# SENSORY_BRIDGE.net
KiCad netlist of a schematic drawn in EAGLE
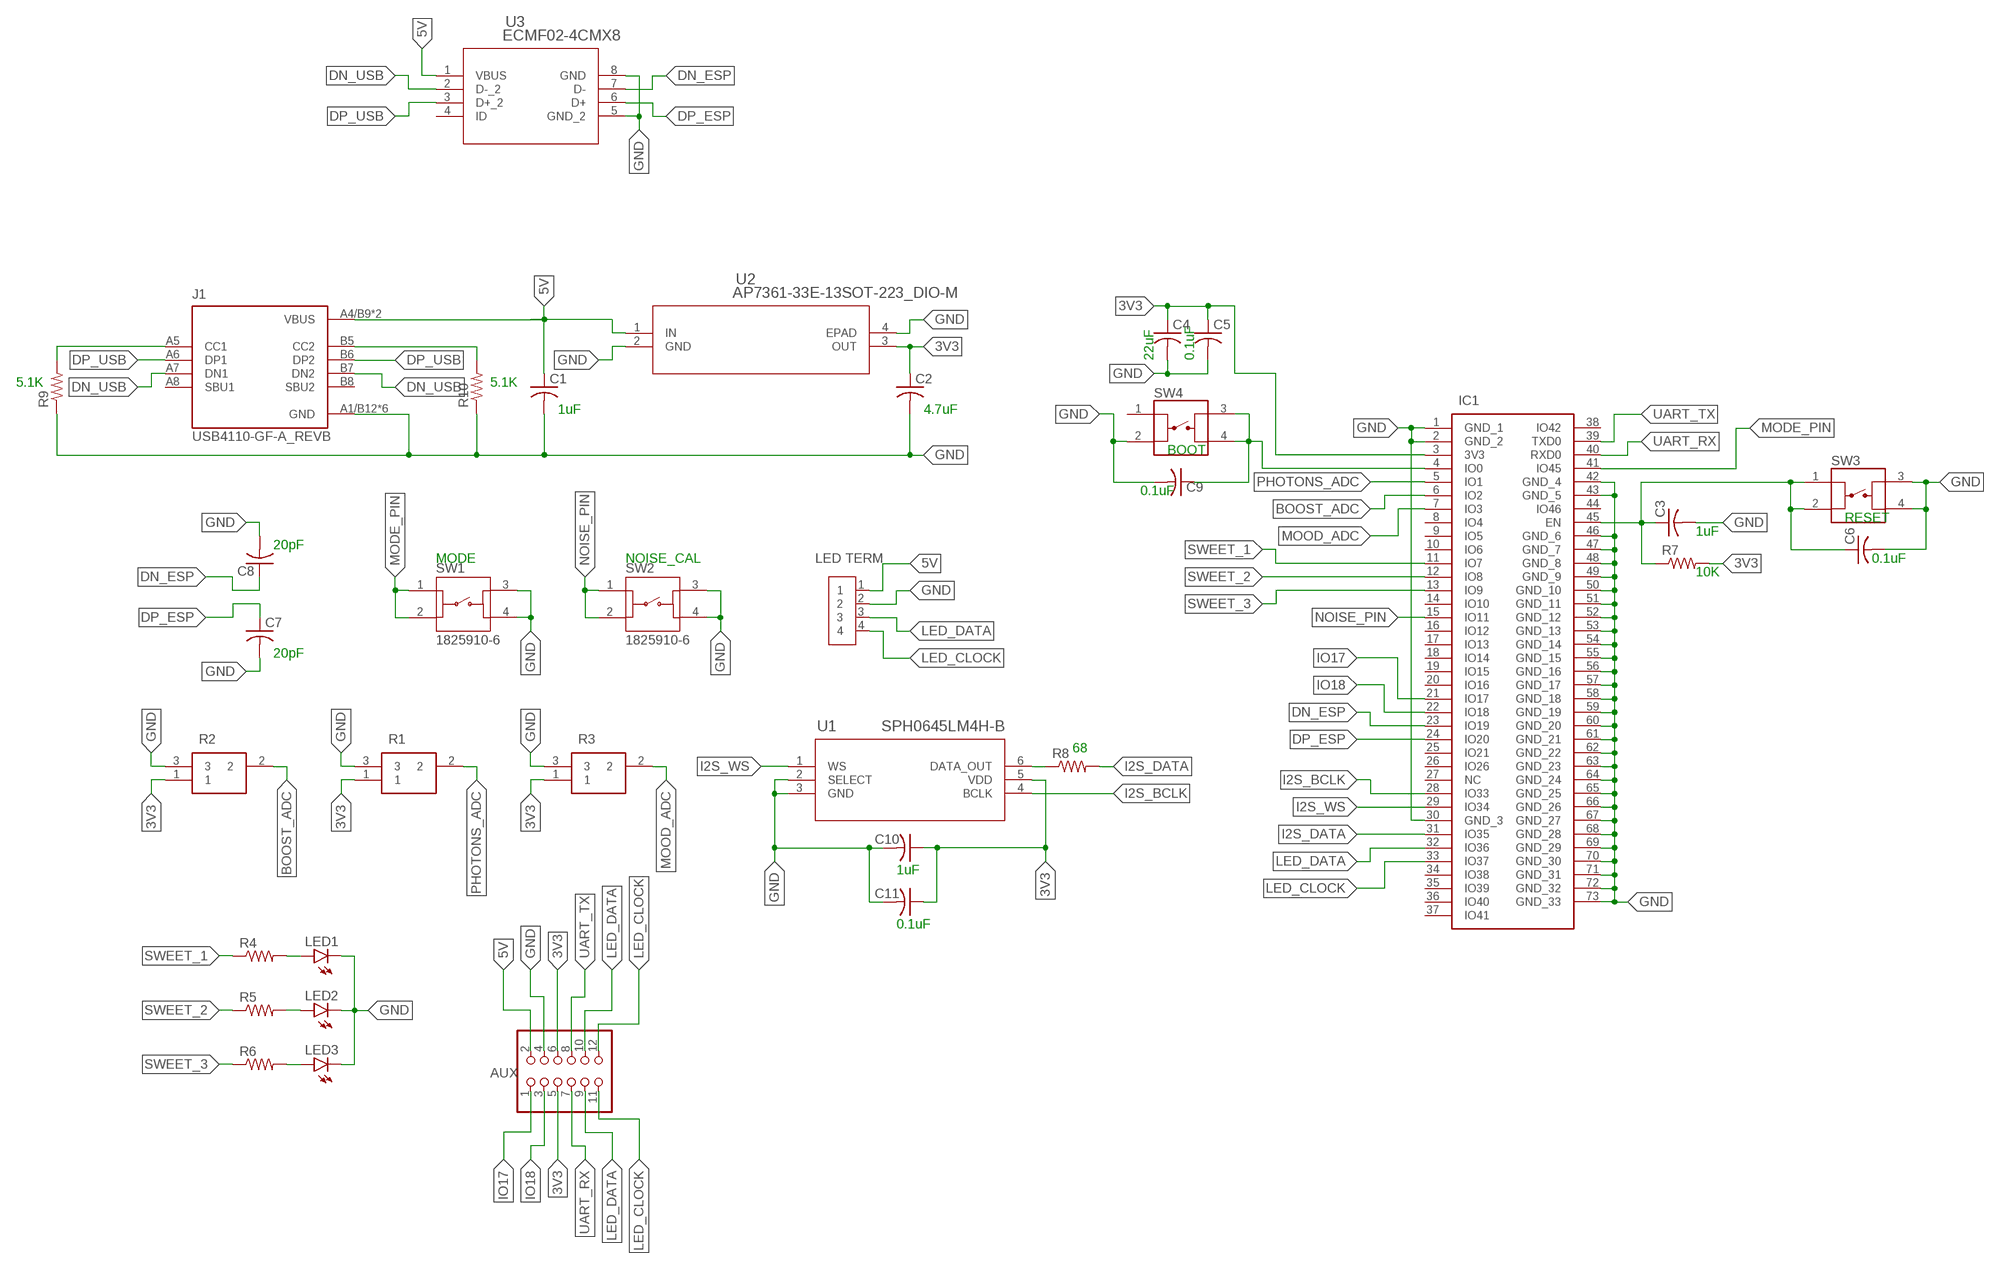
[diagram p0: schematic, sheet 1]

(export (version "E")
  (design (tool "Eeschema 10.0.6"))
  (components
    (comp (ref "C1")
      (value "C-USC0805K")
      (footprint "eagle-import:C0805K")
      (libsource (lib "eagle-import") (part "C-USC0805K"))
    )
    (comp (ref "C2")
      (value "C-USC0805K")
      (footprint "eagle-import:C0805K")
      (libsource (lib "eagle-import") (part "C-USC0805K"))
    )
    (comp (ref "C3")
      (value "C-USC0805K")
      (footprint "eagle-import:C0805K")
      (libsource (lib "eagle-import") (part "C-USC0805K"))
    )
    (comp (ref "C4")
      (value "C-USC0805K")
      (footprint "eagle-import:C0805K")
      (libsource (lib "eagle-import") (part "C-USC0805K"))
    )
    (comp (ref "C5")
      (value "C-USC0805K")
      (footprint "eagle-import:C0805K")
      (libsource (lib "eagle-import") (part "C-USC0805K"))
    )
    (comp (ref "C6")
      (value "C-USC0805K")
      (footprint "eagle-import:C0805K")
      (libsource (lib "eagle-import") (part "C-USC0805K"))
    )
    (comp (ref "C7")
      (value "C-USC0805K")
      (footprint "eagle-import:C0805K")
      (libsource (lib "eagle-import") (part "C-USC0805K"))
    )
    (comp (ref "C8")
      (value "C-USC0805K")
      (footprint "eagle-import:C0805K")
      (libsource (lib "eagle-import") (part "C-USC0805K"))
    )
    (comp (ref "C9")
      (value "C-USC0805K")
      (footprint "eagle-import:C0805K")
      (libsource (lib "eagle-import") (part "C-USC0805K"))
    )
    (comp (ref "C10")
      (value "C-USC0805K")
      (footprint "eagle-import:C0805K")
      (libsource (lib "eagle-import") (part "C-USC0805K"))
    )
    (comp (ref "C11")
      (value "C-USC0805K")
      (footprint "eagle-import:C0805K")
      (libsource (lib "eagle-import") (part "C-USC0805K"))
    )
    (comp (ref "IC1")
      (value "ESP32-S2-MINI-1-N4R2")
      (footprint "eagle-import:ESP32S2MINI1N4R2")
      (fields (field (name "MOUSER_PART_NUMBER") "356-ESP32S2MINI1N4R2"))
      (libsource (lib "eagle-import") (part "ESP32-S2-MINI-1-N4R2"))
    )
    (comp (ref "J1")
      (value "USB4110-GF-A_REVB")
      (footprint "eagle-import:GCT_USB4110-GF-A_REVB")
      (fields
        (field (name "DIGI-KEY_PART_NUMBER") "2073-USB4110-GF-A-1-ND")
        (field (name "MF") "GCT")
        (field (name "MP") "USB4110-GF-A")
      )
      (libsource (lib "eagle-import") (part "USB4110-GF-A_REVB"))
    )
    (comp (ref "J2")
      (value "796949-4")
      (footprint "eagle-import:TE_796949-4")
      (fields (field (name "DIGI-KEY_PART_NUMBER") "796949-4-ND") (field (name "MF") "TE Connectivity"))
      (libsource (lib "eagle-import") (part "796949-4"))
    )
    (comp (ref "JP1")
      (value "PINHD-2X6")
      (footprint "eagle-import:2X06")
      (libsource (lib "eagle-import") (part "PINHD-2X6"))
    )
    (comp (ref "LED1")
      (value "LED3MM")
      (footprint "eagle-import:LED3MM")
      (libsource (lib "eagle-import") (part "LED3MM"))
    )
    (comp (ref "LED2")
      (value "LED3MM")
      (footprint "eagle-import:LED3MM")
      (libsource (lib "eagle-import") (part "LED3MM"))
    )
    (comp (ref "LED3")
      (value "LED3MM")
      (footprint "eagle-import:LED3MM")
      (libsource (lib "eagle-import") (part "LED3MM"))
    )
    (comp (ref "R1")
      (value "3386P-1-103LF")
      (footprint "eagle-import:3386P_1")
      (fields (field (name "MOUSER_PART_NUMBER") "652-3386P-1-103LF"))
      (libsource (lib "eagle-import") (part "3386P-1-103LF"))
    )
    (comp (ref "R2")
      (value "3386P-1-103LF")
      (footprint "eagle-import:3386P_1")
      (fields (field (name "MOUSER_PART_NUMBER") "652-3386P-1-103LF"))
      (libsource (lib "eagle-import") (part "3386P-1-103LF"))
    )
    (comp (ref "R3")
      (value "3386P-1-103LF")
      (footprint "eagle-import:3386P_1")
      (fields (field (name "MOUSER_PART_NUMBER") "652-3386P-1-103LF"))
      (libsource (lib "eagle-import") (part "3386P-1-103LF"))
    )
    (comp (ref "R4")
      (value "R-US_R0805")
      (footprint "eagle-import:R0805")
      (libsource (lib "eagle-import") (part "R-US_R0805"))
    )
    (comp (ref "R5")
      (value "R-US_R0805")
      (footprint "eagle-import:R0805")
      (libsource (lib "eagle-import") (part "R-US_R0805"))
    )
    (comp (ref "R6")
      (value "R-US_R0805")
      (footprint "eagle-import:R0805")
      (libsource (lib "eagle-import") (part "R-US_R0805"))
    )
    (comp (ref "R7")
      (value "R-US_R0805")
      (footprint "eagle-import:R0805")
      (libsource (lib "eagle-import") (part "R-US_R0805"))
    )
    (comp (ref "R8")
      (value "R-US_R0805")
      (footprint "eagle-import:R0805")
      (libsource (lib "eagle-import") (part "R-US_R0805"))
    )
    (comp (ref "R9")
      (value "R-US_R0805")
      (footprint "eagle-import:R0805")
      (libsource (lib "eagle-import") (part "R-US_R0805"))
    )
    (comp (ref "R10")
      (value "R-US_R0805")
      (footprint "eagle-import:R0805")
      (libsource (lib "eagle-import") (part "R-US_R0805"))
    )
    (comp (ref "SW1")
      (value "1825910-6")
      (footprint "eagle-import:SW_1825910-6-4")
      (fields (field (name "DIGI-KEY_PART_NUMBER") "450-1650-ND") (field (name "MF") "TE Connectivity"))
      (libsource (lib "eagle-import") (part "1825910-6"))
    )
    (comp (ref "SW2")
      (value "1825910-6")
      (footprint "eagle-import:SW_1825910-6-4")
      (fields (field (name "DIGI-KEY_PART_NUMBER") "450-1650-ND") (field (name "MF") "TE Connectivity"))
      (libsource (lib "eagle-import") (part "1825910-6"))
    )
    (comp (ref "SW3")
      (value "PTS525SM15SMTR2LFS")
      (footprint "eagle-import:SW_PTS525SM15SMTR2LFS")
      (fields
        (field (name "DIGI-KEY_PART_NUMBER") "CKN9104CT-ND")
        (field (name "MF") "C&K")
        (field (name "MP") "PTS525SM15SMTR2 LFS")
      )
      (libsource (lib "eagle-import") (part "PTS525SM15SMTR2LFS"))
    )
    (comp (ref "SW4")
      (value "PTS525SM15SMTR2LFS")
      (footprint "eagle-import:SW_PTS525SM15SMTR2LFS")
      (fields
        (field (name "DIGI-KEY_PART_NUMBER") "CKN9104CT-ND")
        (field (name "MF") "C&K")
        (field (name "MP") "PTS525SM15SMTR2 LFS")
      )
      (libsource (lib "eagle-import") (part "PTS525SM15SMTR2LFS"))
    )
    (comp (ref "U1")
      (value "SPH0645LM4H-B")
      (footprint "eagle-import:SPH0645LM4H-B_KNO")
      (fields (field (name "COPYRIGHT") "Copyright (C) 2022 Ultra Librarian. All rights reserved."))
      (libsource (lib "eagle-import") (part "SPH0645LM4H-B"))
    )
    (comp (ref "U2")
      (value "AP7361-33E-13SOT-223_DIO-M")
      (footprint "eagle-import:SOT-223_DIO-M")
      (fields
        (field (name "MANUFACTURER_PART_NUMBER") "AP7361-33E-13")
        (field (name "COPYRIGHT") "Copyright (C) 2022 Ultra Librarian. All rights reserved.")
      )
      (libsource (lib "eagle-import") (part "AP7361-33E-13SOT-223_DIO-M"))
    )
    (comp (ref "U3")
      (value "ECMF02-4CMX8")
      (footprint "eagle-import:MICRO_QFN-8L_STM")
      (fields (field (name "COPYRIGHT") "Copyright (C) 2022 Ultra Librarian. All rights reserved."))
      (libsource (lib "eagle-import") (part "ECMF02-4CMX8"))
    )
  )
  (nets
    (net (code "1") (name "3V3") (class "Default")
      (node (ref "C10") (pin "1") (pinfunction "1_1") (pintype "passive"))
      (node (ref "C11") (pin "1") (pinfunction "1_1") (pintype "passive"))
      (node (ref "C2") (pin "1") (pinfunction "1_1") (pintype "passive"))
      (node (ref "C4") (pin "1") (pinfunction "1_1") (pintype "passive"))
      (node (ref "C5") (pin "1") (pinfunction "1_1") (pintype "passive"))
      (node (ref "IC1") (pin "3") (pinfunction "3V3_3") (pintype "bidirectional"))
      (node (ref "JP1") (pin "5") (pinfunction "5_5") (pintype "passive"))
      (node (ref "JP1") (pin "6") (pinfunction "6_6") (pintype "passive"))
      (node (ref "R1") (pin "1") (pinfunction "1_1") (pintype "bidirectional"))
      (node (ref "R2") (pin "1") (pinfunction "1_1") (pintype "bidirectional"))
      (node (ref "R3") (pin "1") (pinfunction "1_1") (pintype "bidirectional"))
      (node (ref "R7") (pin "2") (pinfunction "2_2") (pintype "passive"))
      (node (ref "U1") (pin "5") (pinfunction "VDD_5") (pintype "power_in"))
      (node (ref "U2") (pin "3") (pinfunction "OUT_3") (pintype "output"))
    )
    (net (code "2") (name "5V") (class "Default")
      (node (ref "C1") (pin "1") (pinfunction "1_1") (pintype "passive"))
      (node (ref "J1") (pin "A4/B9") (pinfunction "VBUS_A4/B9") (pintype "power_in"))
      (node (ref "J1") (pin "B4/A9") (pinfunction "VBUS_B4/A9") (pintype "power_in"))
      (node (ref "J2") (pin "1") (pinfunction "1_1") (pintype "passive"))
      (node (ref "JP1") (pin "2") (pinfunction "2_2") (pintype "passive"))
      (node (ref "U2") (pin "1") (pinfunction "IN_1") (pintype "input"))
      (node (ref "U3") (pin "1") (pinfunction "VBUS_1") (pintype "power_in"))
    )
    (net (code "3") (name "BOOST_ADC") (class "Default")
      (node (ref "IC1") (pin "6") (pinfunction "IO2_6") (pintype "bidirectional"))
      (node (ref "R2") (pin "2") (pinfunction "2_2") (pintype "bidirectional"))
    )
    (net (code "4") (name "DN_ESP") (class "Default")
      (node (ref "C8") (pin "1") (pinfunction "1_1") (pintype "passive"))
      (node (ref "IC1") (pin "23") (pinfunction "IO19_23") (pintype "bidirectional"))
      (node (ref "U3") (pin "7") (pinfunction "D-_7") (pintype "bidirectional"))
    )
    (net (code "5") (name "DN_USB") (class "Default")
      (node (ref "J1") (pin "A7") (pinfunction "DN1_A7") (pintype "bidirectional"))
      (node (ref "J1") (pin "B7") (pinfunction "DN2_B7") (pintype "bidirectional"))
      (node (ref "U3") (pin "2") (pinfunction "D-_2_2") (pintype "bidirectional"))
    )
    (net (code "6") (name "DP_ESP") (class "Default")
      (node (ref "C7") (pin "1") (pinfunction "1_1") (pintype "passive"))
      (node (ref "IC1") (pin "24") (pinfunction "IO20_24") (pintype "bidirectional"))
      (node (ref "U3") (pin "6") (pinfunction "D+_6") (pintype "bidirectional"))
    )
    (net (code "7") (name "DP_USB") (class "Default")
      (node (ref "J1") (pin "A6") (pinfunction "DP1_A6") (pintype "bidirectional"))
      (node (ref "J1") (pin "B6") (pinfunction "DP2_B6") (pintype "bidirectional"))
      (node (ref "U3") (pin "3") (pinfunction "D+_2_3") (pintype "bidirectional"))
    )
    (net (code "8") (name "GND") (class "Default")
      (node (ref "C1") (pin "2") (pinfunction "2_2") (pintype "passive"))
      (node (ref "C10") (pin "2") (pinfunction "2_2") (pintype "passive"))
      (node (ref "C11") (pin "2") (pinfunction "2_2") (pintype "passive"))
      (node (ref "C2") (pin "2") (pinfunction "2_2") (pintype "passive"))
      (node (ref "C3") (pin "2") (pinfunction "2_2") (pintype "passive"))
      (node (ref "C4") (pin "2") (pinfunction "2_2") (pintype "passive"))
      (node (ref "C5") (pin "2") (pinfunction "2_2") (pintype "passive"))
      (node (ref "C6") (pin "2") (pinfunction "2_2") (pintype "passive"))
      (node (ref "C7") (pin "2") (pinfunction "2_2") (pintype "passive"))
      (node (ref "C8") (pin "2") (pinfunction "2_2") (pintype "passive"))
      (node (ref "C9") (pin "2") (pinfunction "2_2") (pintype "passive"))
      (node (ref "IC1") (pin "1") (pinfunction "GND_1_1") (pintype "bidirectional"))
      (node (ref "IC1") (pin "2") (pinfunction "GND_2_2") (pintype "bidirectional"))
      (node (ref "IC1") (pin "30") (pinfunction "GND_3_30") (pintype "bidirectional"))
      (node (ref "IC1") (pin "42") (pinfunction "GND_4_42") (pintype "bidirectional"))
      (node (ref "IC1") (pin "43") (pinfunction "GND_5_43") (pintype "bidirectional"))
      (node (ref "IC1") (pin "46") (pinfunction "GND_6_46") (pintype "bidirectional"))
      (node (ref "IC1") (pin "47") (pinfunction "GND_7_47") (pintype "bidirectional"))
      (node (ref "IC1") (pin "48") (pinfunction "GND_8_48") (pintype "bidirectional"))
      (node (ref "IC1") (pin "49") (pinfunction "GND_9_49") (pintype "bidirectional"))
      (node (ref "IC1") (pin "50") (pinfunction "GND_10_50") (pintype "bidirectional"))
      (node (ref "IC1") (pin "51") (pinfunction "GND_11_51") (pintype "bidirectional"))
      (node (ref "IC1") (pin "52") (pinfunction "GND_12_52") (pintype "bidirectional"))
      (node (ref "IC1") (pin "53") (pinfunction "GND_13_53") (pintype "bidirectional"))
      (node (ref "IC1") (pin "54") (pinfunction "GND_14_54") (pintype "bidirectional"))
      (node (ref "IC1") (pin "55") (pinfunction "GND_15_55") (pintype "bidirectional"))
      (node (ref "IC1") (pin "56") (pinfunction "GND_16_56") (pintype "bidirectional"))
      (node (ref "IC1") (pin "57") (pinfunction "GND_17_57") (pintype "bidirectional"))
      (node (ref "IC1") (pin "58") (pinfunction "GND_18_58") (pintype "bidirectional"))
      (node (ref "IC1") (pin "59") (pinfunction "GND_19_59") (pintype "bidirectional"))
      (node (ref "IC1") (pin "60") (pinfunction "GND_20_60") (pintype "bidirectional"))
      (node (ref "IC1") (pin "61") (pinfunction "GND_21_61") (pintype "bidirectional"))
      (node (ref "IC1") (pin "62") (pinfunction "GND_22_62") (pintype "bidirectional"))
      (node (ref "IC1") (pin "63") (pinfunction "GND_23_63") (pintype "bidirectional"))
      (node (ref "IC1") (pin "64") (pinfunction "GND_24_64") (pintype "bidirectional"))
      (node (ref "IC1") (pin "65") (pinfunction "GND_25_65") (pintype "bidirectional"))
      (node (ref "IC1") (pin "66") (pinfunction "GND_26_66") (pintype "bidirectional"))
      (node (ref "IC1") (pin "67") (pinfunction "GND_27_67") (pintype "bidirectional"))
      (node (ref "IC1") (pin "68") (pinfunction "GND_28_68") (pintype "bidirectional"))
      (node (ref "IC1") (pin "69") (pinfunction "GND_29_69") (pintype "bidirectional"))
      (node (ref "IC1") (pin "70") (pinfunction "GND_30_70") (pintype "bidirectional"))
      (node (ref "IC1") (pin "71") (pinfunction "GND_31_71") (pintype "bidirectional"))
      (node (ref "IC1") (pin "72") (pinfunction "GND_32_72") (pintype "bidirectional"))
      (node (ref "IC1") (pin "73") (pinfunction "GND_33_73") (pintype "bidirectional"))
      (node (ref "J1") (pin "A1/B12") (pinfunction "GND_A1/B12") (pintype "power_in"))
      (node (ref "J1") (pin "B1/A12") (pinfunction "GND_B1/A12") (pintype "power_in"))
      (node (ref "J1") (pin "S1") (pinfunction "GND_S1") (pintype "power_in"))
      (node (ref "J1") (pin "S2") (pinfunction "GND_S2") (pintype "power_in"))
      (node (ref "J1") (pin "S3") (pinfunction "GND_S3") (pintype "power_in"))
      (node (ref "J1") (pin "S4") (pinfunction "GND_S4") (pintype "power_in"))
      (node (ref "J2") (pin "2") (pinfunction "2_2") (pintype "passive"))
      (node (ref "JP1") (pin "4") (pinfunction "4_4") (pintype "passive"))
      (node (ref "LED1") (pin "K") (pinfunction "C_K") (pintype "passive"))
      (node (ref "LED2") (pin "K") (pinfunction "C_K") (pintype "passive"))
      (node (ref "LED3") (pin "K") (pinfunction "C_K") (pintype "passive"))
      (node (ref "R1") (pin "3") (pinfunction "3_3") (pintype "bidirectional"))
      (node (ref "R10") (pin "1") (pinfunction "1_1") (pintype "passive"))
      (node (ref "R2") (pin "3") (pinfunction "3_3") (pintype "bidirectional"))
      (node (ref "R3") (pin "3") (pinfunction "3_3") (pintype "bidirectional"))
      (node (ref "R9") (pin "1") (pinfunction "1_1") (pintype "passive"))
      (node (ref "SW1") (pin "3") (pinfunction "3_3") (pintype "passive"))
      (node (ref "SW1") (pin "4") (pinfunction "4_4") (pintype "passive"))
      (node (ref "SW2") (pin "3") (pinfunction "3_3") (pintype "passive"))
      (node (ref "SW2") (pin "4") (pinfunction "4_4") (pintype "passive"))
      (node (ref "SW3") (pin "3") (pinfunction "3_3") (pintype "passive"))
      (node (ref "SW3") (pin "4") (pinfunction "4_4") (pintype "passive"))
      (node (ref "SW4") (pin "2") (pinfunction "2_2") (pintype "passive"))
      (node (ref "U1") (pin "2") (pinfunction "SELECT_2") (pintype "input"))
      (node (ref "U1") (pin "3") (pinfunction "GND_3") (pintype "passive"))
      (node (ref "U2") (pin "2") (pinfunction "GND_2") (pintype "power_in"))
      (node (ref "U2") (pin "4") (pinfunction "EPAD_4") (pintype "passive"))
      (node (ref "U3") (pin "5") (pinfunction "GND_2_5") (pintype "passive"))
      (node (ref "U3") (pin "8") (pinfunction "GND_8") (pintype "passive"))
    )
    (net (code "9") (name "I2S_BCLK") (class "Default")
      (node (ref "IC1") (pin "28") (pinfunction "IO33_28") (pintype "bidirectional"))
      (node (ref "U1") (pin "4") (pinfunction "BCLK_4") (pintype "input"))
    )
    (net (code "10") (name "I2S_DATA") (class "Default")
      (node (ref "IC1") (pin "31") (pinfunction "IO35_31") (pintype "bidirectional"))
      (node (ref "R8") (pin "2") (pinfunction "2_2") (pintype "passive"))
    )
    (net (code "11") (name "I2S_WS") (class "Default")
      (node (ref "IC1") (pin "29") (pinfunction "IO34_29") (pintype "bidirectional"))
      (node (ref "U1") (pin "1") (pinfunction "WS_1") (pintype "input"))
    )
    (net (code "12") (name "IO17") (class "Default")
      (node (ref "IC1") (pin "21") (pinfunction "IO17_21") (pintype "bidirectional"))
      (node (ref "JP1") (pin "1") (pinfunction "1_1") (pintype "passive"))
    )
    (net (code "13") (name "IO18") (class "Default")
      (node (ref "IC1") (pin "22") (pinfunction "IO18_22") (pintype "bidirectional"))
      (node (ref "JP1") (pin "3") (pinfunction "3_3") (pintype "passive"))
    )
    (net (code "14") (name "LED_CLOCK") (class "Default")
      (node (ref "IC1") (pin "33") (pinfunction "IO37_33") (pintype "bidirectional"))
      (node (ref "J2") (pin "4") (pinfunction "4_4") (pintype "passive"))
      (node (ref "JP1") (pin "11") (pinfunction "11_11") (pintype "passive"))
      (node (ref "JP1") (pin "12") (pinfunction "12_12") (pintype "passive"))
    )
    (net (code "15") (name "LED_DATA") (class "Default")
      (node (ref "IC1") (pin "32") (pinfunction "IO36_32") (pintype "bidirectional"))
      (node (ref "J2") (pin "3") (pinfunction "3_3") (pintype "passive"))
      (node (ref "JP1") (pin "10") (pinfunction "10_10") (pintype "passive"))
      (node (ref "JP1") (pin "9") (pinfunction "9_9") (pintype "passive"))
    )
    (net (code "16") (name "MODE_PIN") (class "Default")
      (node (ref "IC1") (pin "41") (pinfunction "IO45_41") (pintype "bidirectional"))
      (node (ref "SW1") (pin "1") (pinfunction "1_1") (pintype "passive"))
      (node (ref "SW1") (pin "2") (pinfunction "2_2") (pintype "passive"))
    )
    (net (code "17") (name "MOOD_ADC") (class "Default")
      (node (ref "IC1") (pin "7") (pinfunction "IO3_7") (pintype "bidirectional"))
      (node (ref "R3") (pin "2") (pinfunction "2_2") (pintype "bidirectional"))
    )
    (net (code "18") (name "NOISE_PIN") (class "Default")
      (node (ref "IC1") (pin "15") (pinfunction "IO11_15") (pintype "bidirectional"))
      (node (ref "SW2") (pin "1") (pinfunction "1_1") (pintype "passive"))
      (node (ref "SW2") (pin "2") (pinfunction "2_2") (pintype "passive"))
    )
    (net (code "19") (name "Net-(IC1-EN)") (class "Default")
      (node (ref "C3") (pin "1") (pinfunction "1_1") (pintype "passive"))
      (node (ref "C6") (pin "1") (pinfunction "1_1") (pintype "passive"))
      (node (ref "IC1") (pin "45") (pinfunction "EN_45") (pintype "bidirectional"))
      (node (ref "R7") (pin "1") (pinfunction "1_1") (pintype "passive"))
      (node (ref "SW3") (pin "1") (pinfunction "1_1") (pintype "passive"))
      (node (ref "SW3") (pin "2") (pinfunction "2_2") (pintype "passive"))
    )
    (net (code "20") (name "Net-(IC1-IO0)") (class "Default")
      (node (ref "C9") (pin "1") (pinfunction "1_1") (pintype "passive"))
      (node (ref "IC1") (pin "4") (pinfunction "IO0_4") (pintype "bidirectional"))
      (node (ref "SW4") (pin "3") (pinfunction "3_3") (pintype "passive"))
      (node (ref "SW4") (pin "4") (pinfunction "4_4") (pintype "passive"))
    )
    (net (code "21") (name "Net-(J1-CC1)") (class "Default")
      (node (ref "J1") (pin "A5") (pinfunction "CC1_A5") (pintype "bidirectional"))
      (node (ref "R9") (pin "2") (pinfunction "2_2") (pintype "passive"))
    )
    (net (code "22") (name "Net-(J1-CC2)") (class "Default")
      (node (ref "J1") (pin "B5") (pinfunction "CC2_B5") (pintype "bidirectional"))
      (node (ref "R10") (pin "2") (pinfunction "2_2") (pintype "passive"))
    )
    (net (code "23") (name "Net-(LED1-PadA)") (class "Default")
      (node (ref "LED1") (pin "A") (pinfunction "A_A") (pintype "passive"))
      (node (ref "R4") (pin "2") (pinfunction "2_2") (pintype "passive"))
    )
    (net (code "24") (name "Net-(LED2-PadA)") (class "Default")
      (node (ref "LED2") (pin "A") (pinfunction "A_A") (pintype "passive"))
      (node (ref "R5") (pin "2") (pinfunction "2_2") (pintype "passive"))
    )
    (net (code "25") (name "Net-(LED3-PadA)") (class "Default")
      (node (ref "LED3") (pin "A") (pinfunction "A_A") (pintype "passive"))
      (node (ref "R6") (pin "2") (pinfunction "2_2") (pintype "passive"))
    )
    (net (code "26") (name "Net-(U1-DATA_OUT)") (class "Default")
      (node (ref "R8") (pin "1") (pinfunction "1_1") (pintype "passive"))
      (node (ref "U1") (pin "6") (pinfunction "DATA_OUT_6") (pintype "output"))
    )
    (net (code "27") (name "PHOTONS_ADC") (class "Default")
      (node (ref "IC1") (pin "5") (pinfunction "IO1_5") (pintype "bidirectional"))
      (node (ref "R1") (pin "2") (pinfunction "2_2") (pintype "bidirectional"))
    )
    (net (code "28") (name "SWEET_1") (class "Default")
      (node (ref "IC1") (pin "11") (pinfunction "IO7_11") (pintype "bidirectional"))
      (node (ref "R4") (pin "1") (pinfunction "1_1") (pintype "passive"))
    )
    (net (code "29") (name "SWEET_2") (class "Default")
      (node (ref "IC1") (pin "12") (pinfunction "IO8_12") (pintype "bidirectional"))
      (node (ref "R5") (pin "1") (pinfunction "1_1") (pintype "passive"))
    )
    (net (code "30") (name "SWEET_3") (class "Default")
      (node (ref "IC1") (pin "13") (pinfunction "IO9_13") (pintype "bidirectional"))
      (node (ref "R6") (pin "1") (pinfunction "1_1") (pintype "passive"))
    )
    (net (code "31") (name "UART_RX") (class "Default")
      (node (ref "IC1") (pin "40") (pinfunction "RXD0_40") (pintype "bidirectional"))
      (node (ref "JP1") (pin "7") (pinfunction "7_7") (pintype "passive"))
    )
    (net (code "32") (name "UART_TX") (class "Default")
      (node (ref "IC1") (pin "39") (pinfunction "TXD0_39") (pintype "bidirectional"))
      (node (ref "JP1") (pin "8") (pinfunction "8_8") (pintype "passive"))
    )
    (net (code "33") (name "unconnected-(IC1-IO4-Pad8)") (class "Default")
      (node (ref "IC1") (pin "8") (pinfunction "IO4_8") (pintype "bidirectional"))
    )
    (net (code "34") (name "unconnected-(IC1-IO5-Pad9)") (class "Default")
      (node (ref "IC1") (pin "9") (pinfunction "IO5_9") (pintype "bidirectional"))
    )
    (net (code "35") (name "unconnected-(IC1-IO6-Pad10)") (class "Default")
      (node (ref "IC1") (pin "10") (pinfunction "IO6_10") (pintype "bidirectional"))
    )
    (net (code "36") (name "unconnected-(IC1-IO10-Pad14)") (class "Default")
      (node (ref "IC1") (pin "14") (pinfunction "IO10_14") (pintype "bidirectional"))
    )
    (net (code "37") (name "unconnected-(IC1-IO12-Pad16)") (class "Default")
      (node (ref "IC1") (pin "16") (pinfunction "IO12_16") (pintype "bidirectional"))
    )
    (net (code "38") (name "unconnected-(IC1-IO13-Pad17)") (class "Default")
      (node (ref "IC1") (pin "17") (pinfunction "IO13_17") (pintype "bidirectional"))
    )
    (net (code "39") (name "unconnected-(IC1-IO14-Pad18)") (class "Default")
      (node (ref "IC1") (pin "18") (pinfunction "IO14_18") (pintype "bidirectional"))
    )
    (net (code "40") (name "unconnected-(IC1-IO15-Pad19)") (class "Default")
      (node (ref "IC1") (pin "19") (pinfunction "IO15_19") (pintype "bidirectional"))
    )
    (net (code "41") (name "unconnected-(IC1-IO16-Pad20)") (class "Default")
      (node (ref "IC1") (pin "20") (pinfunction "IO16_20") (pintype "bidirectional"))
    )
    (net (code "42") (name "unconnected-(IC1-IO21-Pad25)") (class "Default")
      (node (ref "IC1") (pin "25") (pinfunction "IO21_25") (pintype "bidirectional"))
    )
    (net (code "43") (name "unconnected-(IC1-IO26-Pad26)") (class "Default")
      (node (ref "IC1") (pin "26") (pinfunction "IO26_26") (pintype "bidirectional"))
    )
    (net (code "44") (name "unconnected-(IC1-IO38-Pad34)") (class "Default")
      (node (ref "IC1") (pin "34") (pinfunction "IO38_34") (pintype "bidirectional"))
    )
    (net (code "45") (name "unconnected-(IC1-IO39-Pad35)") (class "Default")
      (node (ref "IC1") (pin "35") (pinfunction "IO39_35") (pintype "bidirectional"))
    )
    (net (code "46") (name "unconnected-(IC1-IO40-Pad36)") (class "Default")
      (node (ref "IC1") (pin "36") (pinfunction "IO40_36") (pintype "bidirectional"))
    )
    (net (code "47") (name "unconnected-(IC1-IO41-Pad37)") (class "Default")
      (node (ref "IC1") (pin "37") (pinfunction "IO41_37") (pintype "bidirectional"))
    )
    (net (code "48") (name "unconnected-(IC1-IO42-Pad38)") (class "Default")
      (node (ref "IC1") (pin "38") (pinfunction "IO42_38") (pintype "bidirectional"))
    )
    (net (code "49") (name "unconnected-(IC1-IO46-Pad44)") (class "Default")
      (node (ref "IC1") (pin "44") (pinfunction "IO46_44") (pintype "bidirectional"))
    )
    (net (code "50") (name "unconnected-(IC1-NC-Pad27)") (class "Default")
      (node (ref "IC1") (pin "27") (pinfunction "NC_27") (pintype "no_connect"))
    )
    (net (code "51") (name "unconnected-(J1-SBU1-PadA8)") (class "Default")
      (node (ref "J1") (pin "A8") (pinfunction "SBU1_A8") (pintype "bidirectional"))
    )
    (net (code "52") (name "unconnected-(J1-SBU2-PadB8)") (class "Default")
      (node (ref "J1") (pin "B8") (pinfunction "SBU2_B8") (pintype "bidirectional"))
    )
    (net (code "53") (name "unconnected-(SW4-Pad1)") (class "Default")
      (node (ref "SW4") (pin "1") (pinfunction "1_1") (pintype "passive"))
    )
    (net (code "54") (name "unconnected-(U3-ID-Pad4)") (class "Default")
      (node (ref "U3") (pin "4") (pinfunction "ID_4") (pintype "passive"))
    )
  )
)
